# PixelClockController.net
KiCad netlist of a schematic drawn in Altium Designer
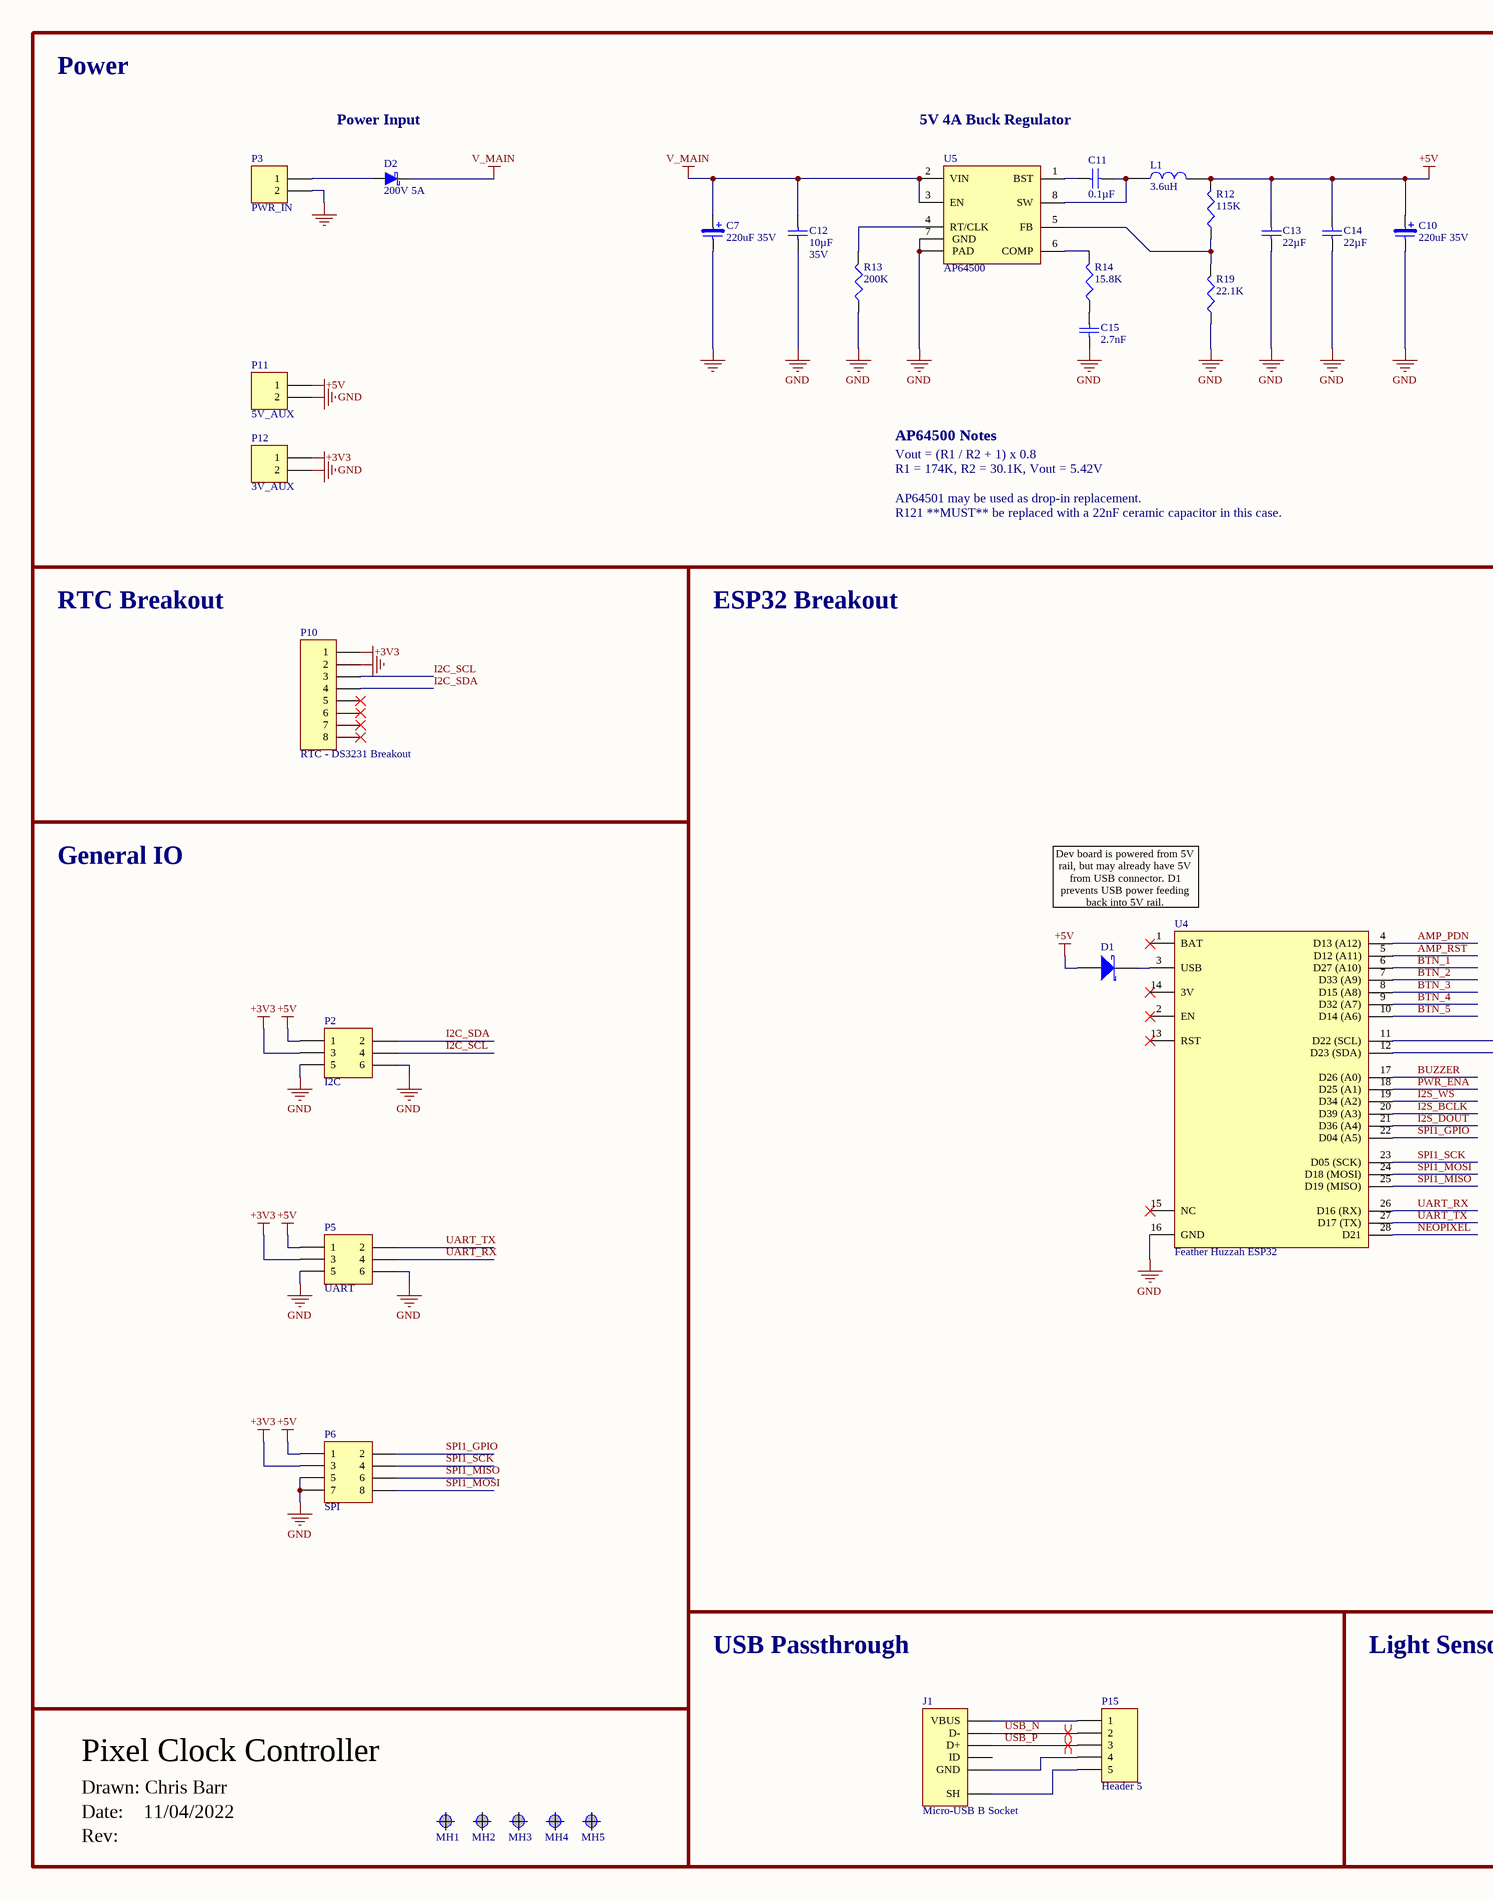
[diagram p0: PixelClockController.SchDoc, left]
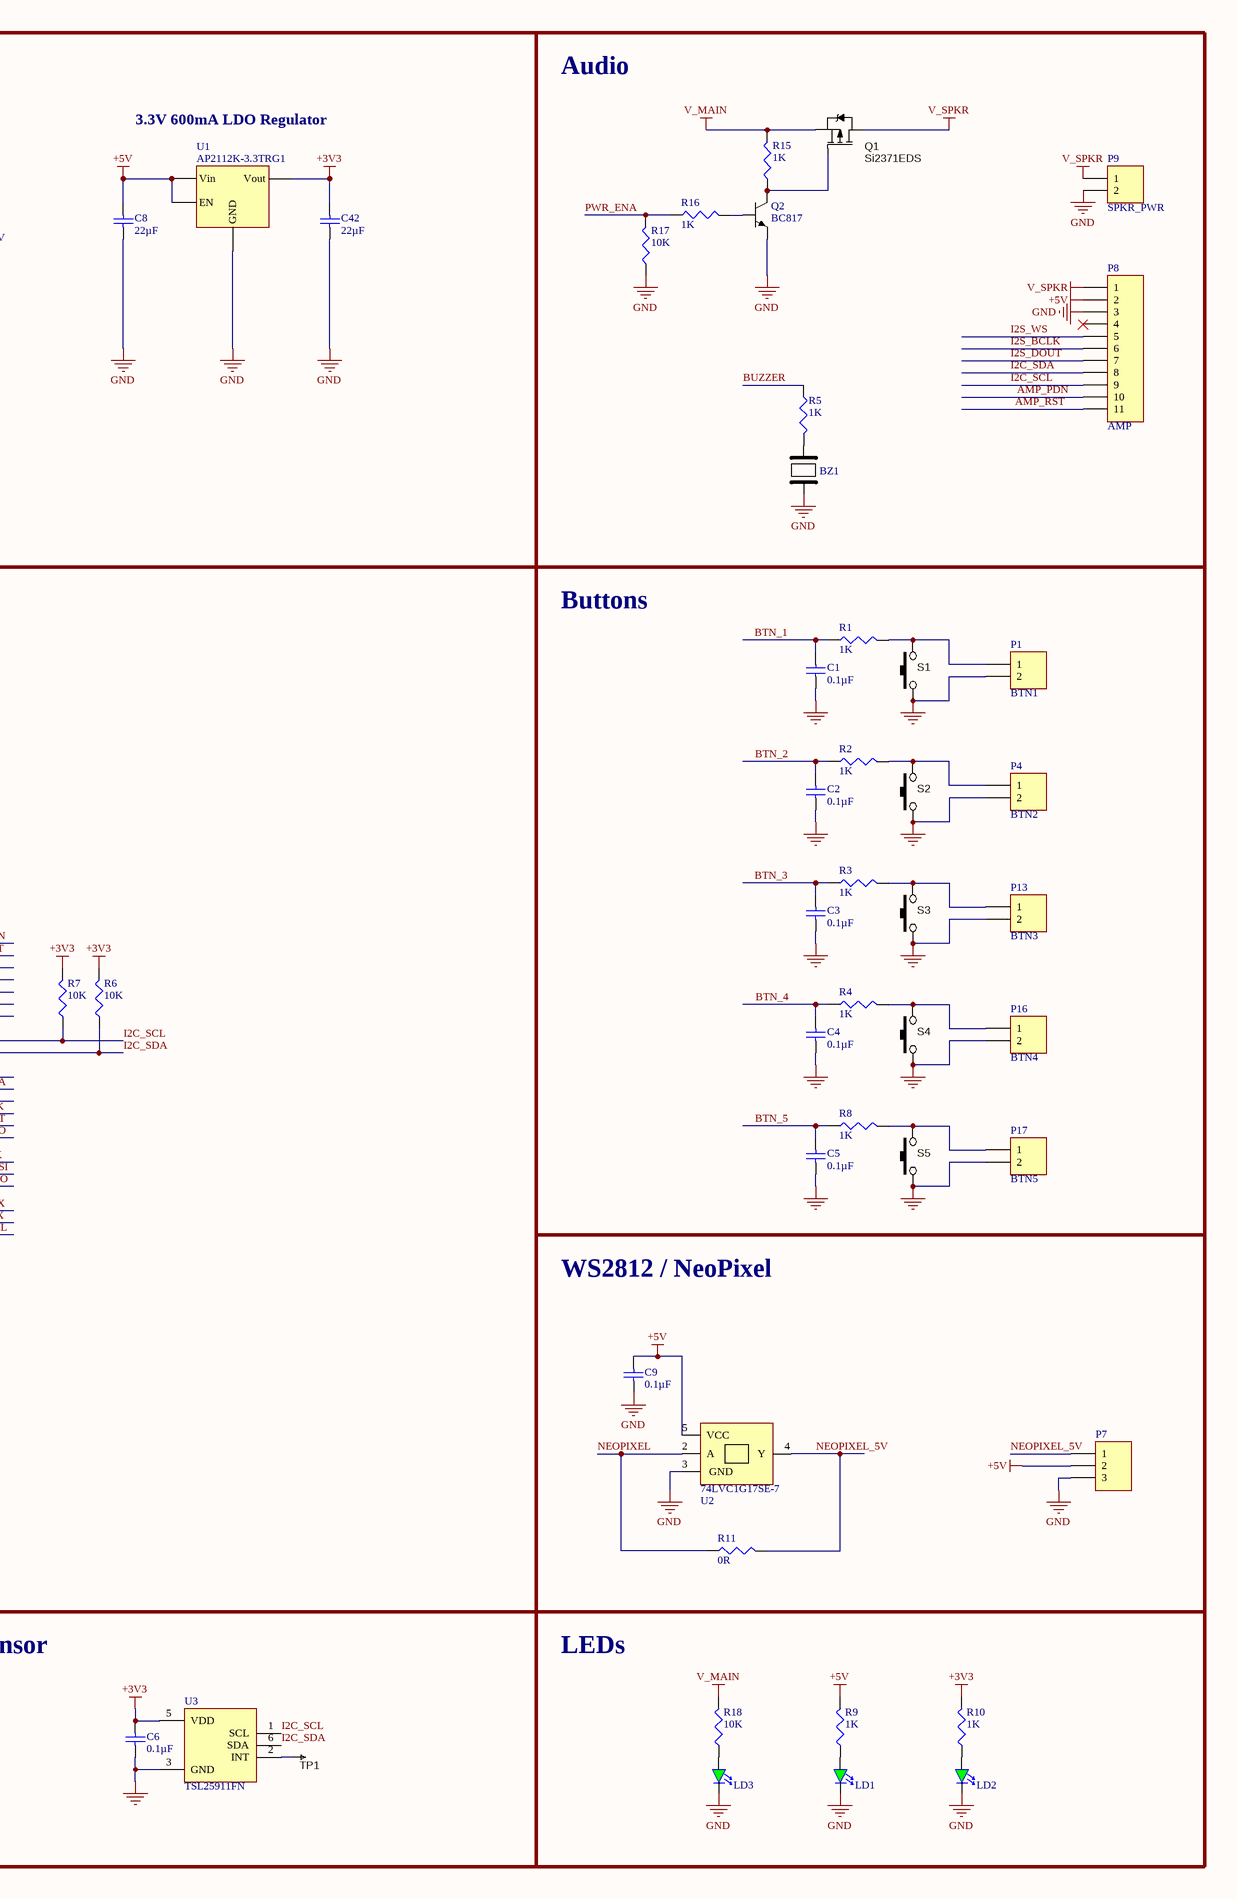
[diagram p1: PixelClockController.SchDoc, right]

(export (version "E")
  (design (tool "Eeschema 10.0.6"))
  (components
    (comp (ref "BZ1")
      (value "Piezo Transducer")
      (footprint "main_library:PKMCS0909E4000-R1")
      (description "AUDIO PIEZO TRANSDUCER 12.5V SMD 9 x 9MM")
      (libsource (lib "main_library") (part "Piezo Transducer"))
    )
    (comp (ref "C1")
      (value "0.1µF")
      (footprint "CAPC1608X90N")
      (description "CAP CER 0.1UF 50V X7R 0603")
      (fields (field (name "VOLTAGE") "50V") (field (name "TOLERANCE") "±10%"))
      (libsource (lib "Ceramic Cap DBLIB") (part "Capacitor"))
    )
    (comp (ref "C2")
      (value "0.1µF")
      (footprint "CAPC1608X90N")
      (description "CAP CER 0.1UF 50V X7R 0603")
      (fields (field (name "VOLTAGE") "50V") (field (name "TOLERANCE") "±10%"))
      (libsource (lib "Ceramic Cap DBLIB") (part "Capacitor"))
    )
    (comp (ref "C3")
      (value "0.1µF")
      (footprint "CAPC1608X90N")
      (description "CAP CER 0.1UF 50V X7R 0603")
      (fields (field (name "VOLTAGE") "50V") (field (name "TOLERANCE") "±10%"))
      (libsource (lib "Ceramic Cap DBLIB") (part "Capacitor"))
    )
    (comp (ref "C4")
      (value "0.1µF")
      (footprint "CAPC1608X90N")
      (description "CAP CER 0.1UF 50V X7R 0603")
      (fields (field (name "VOLTAGE") "50V") (field (name "TOLERANCE") "±10%"))
      (libsource (lib "Ceramic Cap DBLIB") (part "Capacitor"))
    )
    (comp (ref "C5")
      (value "0.1µF")
      (footprint "CAPC1608X90N")
      (description "CAP CER 0.1UF 50V X7R 0603")
      (fields (field (name "VOLTAGE") "50V") (field (name "TOLERANCE") "±10%"))
      (libsource (lib "Ceramic Cap DBLIB") (part "Capacitor"))
    )
    (comp (ref "C6")
      (value "0.1µF")
      (footprint "CAPC1608X90N")
      (description "CAP CER 0.1UF 50V X7R 0603")
      (fields (field (name "VOLTAGE") "50V") (field (name "TOLERANCE") "±10%"))
      (libsource (lib "Ceramic Cap DBLIB") (part "Capacitor"))
    )
    (comp (ref "C7")
      (value "220uF 35V")
      (footprint "CAPAE250P680X1220_VERT")
      (description "CAP ALUM 220UF 20% 35V RADIAL")
      (fields (field (name "Comment") "CapE-8.0-THT-220uF-35V") (field (name "PUBLISHER") "Altium Limited"))
      (libsource (lib "main_library") (part "CapE-8.0-THT-220uF-35V"))
    )
    (comp (ref "C8")
      (value "22µF")
      (footprint "CAPC3216X100N")
      (description "CAP CER 22UF 16V X5R 1206")
      (fields (field (name "VOLTAGE") "16V") (field (name "TOLERANCE") "±10%"))
      (libsource (lib "Ceramic Cap DBLIB") (part "Capacitor"))
    )
    (comp (ref "C9")
      (value "0.1µF")
      (footprint "CAPC1608X90N")
      (description "CAP CER 0.1UF 50V X7R 0603")
      (fields (field (name "VOLTAGE") "50V") (field (name "TOLERANCE") "±10%"))
      (libsource (lib "Ceramic Cap DBLIB") (part "Capacitor"))
    )
    (comp (ref "C10")
      (value "220uF 35V")
      (footprint "CAPAE250P680X1220_VERT")
      (description "CAP ALUM 220UF 20% 35V RADIAL")
      (fields (field (name "Comment") "CapE-8.0-THT-220uF-35V") (field (name "PUBLISHER") "Altium Limited"))
      (libsource (lib "main_library") (part "CapE-8.0-THT-220uF-35V"))
    )
    (comp (ref "C11")
      (value "0.1µF")
      (footprint "CAPC1608X90N")
      (description "CAP CER 0.1UF 50V X7R 0603")
      (fields (field (name "VOLTAGE") "50V") (field (name "TOLERANCE") "±10%"))
      (libsource (lib "Ceramic Cap DBLIB") (part "Capacitor"))
    )
    (comp (ref "C12")
      (value "10µF")
      (footprint "CAPC3225X220N")
      (description "CAP CER 10UF 35V X7R 1210")
      (fields
        (field (name "TOLERANCE") "±10%")
        (field (name "VOLTAGE") "35V")
        (field (name "Comment") "Capacitor")
      )
      (libsource (lib "Ceramic Cap DBLIB") (part "Capacitor"))
    )
    (comp (ref "C13")
      (value "22µF")
      (footprint "CAPC3216X100N")
      (description "CAP CER 22UF 16V X5R 1206")
      (fields (field (name "VOLTAGE") "16V") (field (name "TOLERANCE") "±10%"))
      (libsource (lib "Ceramic Cap DBLIB") (part "Capacitor"))
    )
    (comp (ref "C14")
      (value "22µF")
      (footprint "CAPC3216X100N")
      (description "CAP CER 22UF 16V X5R 1206")
      (fields (field (name "VOLTAGE") "16V") (field (name "TOLERANCE") "±10%"))
      (libsource (lib "Ceramic Cap DBLIB") (part "Capacitor"))
    )
    (comp (ref "C15")
      (value "2.7nF")
      (footprint "CAPC1608X90N")
      (description "CAP CER 2700PF 50V X7R 0603")
      (fields (field (name "VOLTAGE") "100V") (field (name "TOLERANCE") "±10%"))
      (libsource (lib "Ceramic Cap DBLIB") (part "Capacitor"))
    )
    (comp (ref "C42")
      (value "22µF")
      (footprint "CAPC3216X100N")
      (description "CAP CER 22UF 16V X5R 1206")
      (fields (field (name "VOLTAGE") "16V") (field (name "TOLERANCE") "±10%"))
      (libsource (lib "Ceramic Cap DBLIB") (part "Capacitor"))
    )
    (comp (ref "D1")
      (value "~")
      (footprint "DIOM2616X08N")
      (description "DIODE SCHOTTKY 40V 2A SOD123F")
      (fields (field (name "PUBLISHER") "Altium Limited"))
      (libsource (lib "picoprint_library") (part "Diode Schottky 2A 40V (SS24FL)"))
    )
    (comp (ref "D2")
      (value "200V 5A")
      (footprint "DO-214AA")
      (description "DIODE SCHOTTKY 200V 5A SMB")
      (fields (field (name "Comment") "Diode SK520BTR") (field (name "PUBLISHER") "Altium Limited"))
      (libsource (lib "main_library") (part "Diode SK520BTR"))
    )
    (comp (ref "J1")
      (value "Micro-USB B Socket")
      (footprint "USB3131-XX-0230-X_revB")
      (description "MICRO B SKT, VERTICAL, TH, 30\",")
      (libsource (lib "main_library") (part "Micro-USB B Socket Vertical"))
    )
    (comp (ref "L1")
      (value "3.6uH")
      (footprint "main_library:INDUCTOR_NR8040")
      (description "FIXED IND 3.6UH 4.9A 19.5 MOHM")
      (fields (field (name "Comment") "Inductor SMD 3.6uH 4.9A") (field (name "PUBLISHER") "Altium Limited"))
      (libsource (lib "main_library") (part "Inductor SMD 3.6uH 4.9A"))
    )
    (comp (ref "LD1")
      (value "LEDG  0603")
      (footprint "LED 1608-0603")
      (description "LED GREEN CLEAR CHIP SMD 0603")
      (libsource (lib "main_library") (part "LEDG  0603"))
    )
    (comp (ref "LD2")
      (value "LEDG  0603")
      (footprint "LED 1608-0603")
      (description "LED GREEN CLEAR CHIP SMD 0603")
      (libsource (lib "main_library") (part "LEDG  0603"))
    )
    (comp (ref "LD3")
      (value "LEDG  0603")
      (footprint "LED 1608-0603")
      (description "LED GREEN CLEAR CHIP SMD 0603")
      (libsource (lib "main_library") (part "LEDG  0603"))
    )
    (comp (ref "MH1")
      (value "Screw Hole")
      (footprint "M3-Hole-2")
      (libsource (lib "main_library") (part "Screw Hole"))
    )
    (comp (ref "MH2")
      (value "Screw Hole")
      (footprint "M3-Hole-2")
      (libsource (lib "main_library") (part "Screw Hole"))
    )
    (comp (ref "MH3")
      (value "Screw Hole")
      (footprint "M3-Hole-2")
      (libsource (lib "main_library") (part "Screw Hole"))
    )
    (comp (ref "MH4")
      (value "Screw Hole")
      (footprint "M3-Hole-2")
      (libsource (lib "main_library") (part "Screw Hole"))
    )
    (comp (ref "MH5")
      (value "Screw Hole")
      (footprint "M3-Hole-2")
      (libsource (lib "main_library") (part "Screw Hole"))
    )
    (comp (ref "P1")
      (value "BTN1")
      (footprint "HDR1X2-HEADER")
      (description "Header, 2-Pin")
      (libsource (lib "main_library") (part "Header 1X2"))
    )
    (comp (ref "P2")
      (value "I2C")
      (footprint "HDR2X3-Header")
      (description "Header, 3-Pin, Dual row")
      (libsource (lib "main_library") (part "Header 2X3"))
    )
    (comp (ref "P3")
      (value "PWR_IN")
      (footprint "HDR1X2-HEADER")
      (description "Header, 2-Pin")
      (libsource (lib "") (part "Header 1X2_1"))
    )
    (comp (ref "P4")
      (value "BTN2")
      (footprint "HDR1X2-HEADER")
      (description "Header, 2-Pin")
      (libsource (lib "main_library") (part "Header 1X2"))
    )
    (comp (ref "P5")
      (value "UART")
      (footprint "HDR2X3-Header")
      (description "Header, 3-Pin, Dual row")
      (libsource (lib "main_library") (part "Header 2X3"))
    )
    (comp (ref "P6")
      (value "SPI")
      (footprint "HDR2X4-HEADER")
      (description "Header, 4-Pin, Dual row")
      (libsource (lib "main_library") (part "Header 2X4"))
    )
    (comp (ref "P7")
      (value "Header 3")
      (footprint "HDR1X3-HEADER")
      (description "Header, 3-Pin")
      (libsource (lib "main_library") (part "Header 1X3"))
    )
    (comp (ref "P8")
      (value "AMP")
      (footprint "HDR1X11")
      (description "Header, 11-Pin")
      (fields (field (name "PUBLISHER") "Altium Limited"))
      (libsource (lib "Miscellaneous Connectors") (part "Header 11"))
    )
    (comp (ref "P9")
      (value "SPKR_PWR")
      (footprint "HDR1X2-HEADER")
      (description "Header, 2-Pin")
      (libsource (lib "main_library") (part "Header 1X2"))
    )
    (comp (ref "P10")
      (value "RTC - DS3231 Breakout")
      (footprint "HDR1X8-HEADER")
      (description "Header, 8-Pin")
      (libsource (lib "main_library") (part "Header 1X8"))
    )
    (comp (ref "P11")
      (value "5V_AUX")
      (footprint "HDR1X2-HEADER")
      (description "Header, 2-Pin")
      (libsource (lib "") (part "Header 1X2_1"))
    )
    (comp (ref "P12")
      (value "3V_AUX")
      (footprint "HDR1X2-HEADER")
      (description "Header, 2-Pin")
      (libsource (lib "") (part "Header 1X2_1"))
    )
    (comp (ref "P13")
      (value "BTN3")
      (footprint "HDR1X2-HEADER")
      (description "Header, 2-Pin")
      (libsource (lib "main_library") (part "Header 1X2"))
    )
    (comp (ref "P15")
      (value "Header 5")
      (footprint "HDR1X5")
      (description "Header, 5-Pin")
      (fields (field (name "PUBLISHER") "Altium Limited"))
      (libsource (lib "Miscellaneous Connectors") (part "Header 5"))
    )
    (comp (ref "P16")
      (value "BTN4")
      (footprint "HDR1X2-HEADER")
      (description "Header, 2-Pin")
      (libsource (lib "main_library") (part "Header 1X2"))
    )
    (comp (ref "P17")
      (value "BTN5")
      (footprint "HDR1X2-HEADER")
      (description "Header, 2-Pin")
      (libsource (lib "main_library") (part "Header 1X2"))
    )
    (comp (ref "Q1")
      (value "Si2371EDS")
      (footprint "SOT23-3 New")
      (description "MOSFET SMD P-CH 30V 4.8A SOT-23-3")
      (libsource (lib "main_library") (part "MOSFET - Si2371EDS"))
    )
    (comp (ref "Q2")
      (value "BC817")
      (footprint "SOT23-3 New")
      (description "TRANS NPN 45V 500MA TO236AB")
      (libsource (lib "main_library") (part "Transistor - NPN - 45V 500MA - BC817"))
    )
    (comp (ref "R1")
      (value "1K")
      (footprint "RES 1608-0603")
      (description "RES SMD 1K OHM 1% 1/10W 0603")
      (fields
        (field (name "TOLERANCE") "±1%")
        (field (name "Comment") "Resistor")
        (field (name "PUBLISHER") "Altium Limited")
      )
      (libsource (lib "Database_Libs1") (part "Resistor"))
    )
    (comp (ref "R2")
      (value "1K")
      (footprint "RES 1608-0603")
      (description "RES SMD 1K OHM 1% 1/10W 0603")
      (fields
        (field (name "TOLERANCE") "±1%")
        (field (name "Comment") "Resistor")
        (field (name "PUBLISHER") "Altium Limited")
      )
      (libsource (lib "Database_Libs1") (part "Resistor"))
    )
    (comp (ref "R3")
      (value "1K")
      (footprint "RES 1608-0603")
      (description "RES SMD 1K OHM 1% 1/10W 0603")
      (fields
        (field (name "TOLERANCE") "±1%")
        (field (name "Comment") "Resistor")
        (field (name "PUBLISHER") "Altium Limited")
      )
      (libsource (lib "Database_Libs1") (part "Resistor"))
    )
    (comp (ref "R4")
      (value "1K")
      (footprint "RES 1608-0603")
      (description "RES SMD 1K OHM 1% 1/10W 0603")
      (fields
        (field (name "TOLERANCE") "±1%")
        (field (name "Comment") "Resistor")
        (field (name "PUBLISHER") "Altium Limited")
      )
      (libsource (lib "Database_Libs1") (part "Resistor"))
    )
    (comp (ref "R5")
      (value "1K")
      (footprint "RES 1608-0603")
      (description "RES SMD 1K OHM 1% 1/10W 0603")
      (fields
        (field (name "TOLERANCE") "±1%")
        (field (name "Comment") "Resistor")
        (field (name "PUBLISHER") "Altium Limited")
      )
      (libsource (lib "Database_Libs1") (part "Resistor"))
    )
    (comp (ref "R6")
      (value "10K")
      (footprint "RES 1608-0603")
      (description "RES SMD 10K OHM 1% 1/10W 0603")
      (fields
        (field (name "TOLERANCE") "±1%")
        (field (name "Comment") "Resistor")
        (field (name "PUBLISHER") "Altium Limited")
      )
      (libsource (lib "Database_Libs1") (part "Resistor"))
    )
    (comp (ref "R7")
      (value "10K")
      (footprint "RES 1608-0603")
      (description "RES SMD 10K OHM 1% 1/10W 0603")
      (fields
        (field (name "TOLERANCE") "±1%")
        (field (name "Comment") "Resistor")
        (field (name "PUBLISHER") "Altium Limited")
      )
      (libsource (lib "Database_Libs1") (part "Resistor"))
    )
    (comp (ref "R8")
      (value "1K")
      (footprint "RES 1608-0603")
      (description "RES SMD 1K OHM 1% 1/10W 0603")
      (fields
        (field (name "TOLERANCE") "±1%")
        (field (name "Comment") "Resistor")
        (field (name "PUBLISHER") "Altium Limited")
      )
      (libsource (lib "Database_Libs1") (part "Resistor"))
    )
    (comp (ref "R9")
      (value "1K")
      (footprint "RES 1608-0603")
      (description "RES SMD 1K OHM 1% 1/10W 0603")
      (fields
        (field (name "TOLERANCE") "±1%")
        (field (name "Comment") "Resistor")
        (field (name "PUBLISHER") "Altium Limited")
      )
      (libsource (lib "Database_Libs1") (part "Resistor"))
    )
    (comp (ref "R10")
      (value "1K")
      (footprint "RES 1608-0603")
      (description "RES SMD 1K OHM 1% 1/10W 0603")
      (fields
        (field (name "TOLERANCE") "±1%")
        (field (name "Comment") "Resistor")
        (field (name "PUBLISHER") "Altium Limited")
      )
      (libsource (lib "Database_Libs1") (part "Resistor"))
    )
    (comp (ref "R11")
      (value "0R")
      (footprint "RES 1608-0603")
      (description "RES 0 OHM JUMPER 1/10W 0603")
      (fields (field (name "Comment") "Res-0603-0R") (field (name "PUBLISHER") "Altium Limited"))
      (libsource (lib "main_library") (part "Res-0603-0R"))
    )
    (comp (ref "R12")
      (value "115K")
      (footprint "RES 1608-0603")
      (description "RES SMD 115K OHM 1% 1/10W 0603")
      (fields
        (field (name "TOLERANCE") "±1%")
        (field (name "Comment") "Resistor")
        (field (name "PUBLISHER") "Altium Limited")
      )
      (libsource (lib "Database_Libs1") (part "Resistor"))
    )
    (comp (ref "R13")
      (value "200K")
      (footprint "RES 1608-0603")
      (description "RES SMD 200K OHM 1% 1/10W 0603")
      (fields
        (field (name "TOLERANCE") "±1%")
        (field (name "Comment") "Resistor")
        (field (name "PUBLISHER") "Altium Limited")
      )
      (libsource (lib "Database_Libs1") (part "Resistor"))
    )
    (comp (ref "R14")
      (value "15.8K")
      (footprint "RES 1608-0603")
      (description "RES SMD 15.8K OHM 1% 1/10W 0603")
      (fields
        (field (name "TOLERANCE") "±1%")
        (field (name "Comment") "Resistor")
        (field (name "PUBLISHER") "Altium Limited")
      )
      (libsource (lib "Database_Libs1") (part "Resistor"))
    )
    (comp (ref "R15")
      (value "1K")
      (footprint "RES 1608-0603")
      (description "RES SMD 1K OHM 1% 1/10W 0603")
      (fields
        (field (name "TOLERANCE") "±1%")
        (field (name "Comment") "Resistor")
        (field (name "PUBLISHER") "Altium Limited")
      )
      (libsource (lib "Database_Libs1") (part "Resistor"))
    )
    (comp (ref "R16")
      (value "1K")
      (footprint "RES 1608-0603")
      (description "RES SMD 1K OHM 1% 1/10W 0603")
      (fields
        (field (name "TOLERANCE") "±1%")
        (field (name "Comment") "Resistor")
        (field (name "PUBLISHER") "Altium Limited")
      )
      (libsource (lib "Database_Libs1") (part "Resistor"))
    )
    (comp (ref "R17")
      (value "10K")
      (footprint "RES 1608-0603")
      (description "RES SMD 10K OHM 1% 1/10W 0603")
      (fields
        (field (name "TOLERANCE") "±1%")
        (field (name "Comment") "Resistor")
        (field (name "PUBLISHER") "Altium Limited")
      )
      (libsource (lib "Database_Libs1") (part "Resistor"))
    )
    (comp (ref "R18")
      (value "10K")
      (footprint "RES 1608-0603")
      (description "RES SMD 10K OHM 1% 1/10W 0603")
      (fields
        (field (name "TOLERANCE") "±1%")
        (field (name "Comment") "Resistor")
        (field (name "PUBLISHER") "Altium Limited")
      )
      (libsource (lib "Database_Libs1") (part "Resistor"))
    )
    (comp (ref "R19")
      (value "22.1K")
      (footprint "RES 1608-0603")
      (description "RES SMD 22.1K OHM 1% 1/10W 0603")
      (fields
        (field (name "TOLERANCE") "±1%")
        (field (name "Comment") "Resistor")
        (field (name "PUBLISHER") "Altium Limited")
      )
      (libsource (lib "Database_Libs1") (part "Resistor"))
    )
    (comp (ref "S1")
      (value "SW_THT_PB_4.3mm")
      (footprint "TACT-SWITCH-TS1143")
      (description "6 X 6 MM, 12 MM ACTUATOR HEIGHT")
      (libsource (lib "PBL - Switches") (part "SW_THT_PB_4.3mm"))
    )
    (comp (ref "S2")
      (value "SW_THT_PB_4.3mm")
      (footprint "TACT-SWITCH-TS1143")
      (description "6 X 6 MM, 12 MM ACTUATOR HEIGHT")
      (libsource (lib "PBL - Switches") (part "SW_THT_PB_4.3mm"))
    )
    (comp (ref "S3")
      (value "SW_THT_PB_4.3mm")
      (footprint "TACT-SWITCH-TS1143")
      (description "6 X 6 MM, 12 MM ACTUATOR HEIGHT")
      (libsource (lib "PBL - Switches") (part "SW_THT_PB_4.3mm"))
    )
    (comp (ref "S4")
      (value "SW_THT_PB_4.3mm")
      (footprint "TACT-SWITCH-TS1143")
      (description "6 X 6 MM, 12 MM ACTUATOR HEIGHT")
      (libsource (lib "PBL - Switches") (part "SW_THT_PB_4.3mm"))
    )
    (comp (ref "S5")
      (value "SW_THT_PB_4.3mm")
      (footprint "TACT-SWITCH-TS1143")
      (description "6 X 6 MM, 12 MM ACTUATOR HEIGHT")
      (libsource (lib "PBL - Switches") (part "SW_THT_PB_4.3mm"))
    )
    (comp (ref "TP1")
      (value "TESTPOINT")
      (footprint "TP-R60")
      (description "SMD test pin")
      (libsource (lib "PBL - Test Points") (part "TESTPOINT"))
    )
    (comp (ref "U1")
      (value "AP2112K-3.3TRG1")
      (footprint "SOT23-5")
      (description "IC REG LINEAR 3.3V 600MA SOT25")
      (libsource (lib "picoprint_library") (part "Regulator - AP2112K 3.3V Linear Regulator"))
    )
    (comp (ref "U2")
      (value "74LVC1G17SE-7")
      (footprint "SOT353")
      (description "IC BUF NON-INVERT 5.5V SOT353")
      (libsource (lib "picoprint_library") (part "Buffer Non-Inverting Schmitt Trigger 74LVC1G17SE-7"))
    )
    (comp (ref "U3")
      (value "TSL25911FN")
      (footprint "SON65P200X70-6N")
      (description "SENSOR OPT AMBIENT 6DFN")
      (libsource (lib "main_library") (part "IC - Optical Sensor Ambient - I²C 6-WFDFN"))
    )
    (comp (ref "U4")
      (value "Feather Huzzah ESP32")
      (footprint "Adafruit Feather Huzzah ESP32")
      (libsource (lib "main_library") (part "Adafruit Feather - ESP32 Huzzah"))
    )
    (comp (ref "U5")
      (value "AP64500")
      (footprint "main_library:SOIC127P600X140_HS-9N")
      (description "IC DCDC CONV HV BUCK SO-8EP")
      (libsource (lib "main_library") (part "Regulator - AP64500 Buck Regulator"))
    )
  )
  (nets
    (net (code "1") (name "+3V3") (class "Default")
      (node (ref "C42") (pin "2") (pinfunction "2_2") (pintype "passive"))
      (node (ref "C6") (pin "2") (pinfunction "2_2") (pintype "passive"))
      (node (ref "P10") (pin "1") (pinfunction "1_1") (pintype "passive"))
      (node (ref "P12") (pin "1") (pinfunction "1_1") (pintype "passive"))
      (node (ref "P2") (pin "3") (pinfunction "3_3") (pintype "passive"))
      (node (ref "P5") (pin "3") (pinfunction "3_3") (pintype "passive"))
      (node (ref "P6") (pin "3") (pinfunction "3_3") (pintype "passive"))
      (node (ref "R10") (pin "2") (pinfunction "2_2") (pintype "passive"))
      (node (ref "R6") (pin "2") (pinfunction "2_2") (pintype "passive"))
      (node (ref "R7") (pin "2") (pinfunction "2_2") (pintype "passive"))
      (node (ref "U1") (pin "5") (pinfunction "Vout_5") (pintype "passive"))
      (node (ref "U3") (pin "5") (pinfunction "VDD_5") (pintype "passive"))
    )
    (net (code "2") (name "+5V") (class "Default")
      (node (ref "C10") (pin "1") (pinfunction "1_1") (pintype "passive"))
      (node (ref "C13") (pin "2") (pinfunction "2_2") (pintype "passive"))
      (node (ref "C14") (pin "2") (pinfunction "2_2") (pintype "passive"))
      (node (ref "C8") (pin "2") (pinfunction "2_2") (pintype "passive"))
      (node (ref "C9") (pin "2") (pinfunction "2_2") (pintype "passive"))
      (node (ref "D1") (pin "A") (pinfunction "A_A") (pintype "passive"))
      (node (ref "L1") (pin "2") (pinfunction "2_2") (pintype "passive"))
      (node (ref "P11") (pin "1") (pinfunction "1_1") (pintype "passive"))
      (node (ref "P2") (pin "1") (pinfunction "1_1") (pintype "passive"))
      (node (ref "P5") (pin "1") (pinfunction "1_1") (pintype "passive"))
      (node (ref "P6") (pin "1") (pinfunction "1_1") (pintype "passive"))
      (node (ref "P7") (pin "2") (pinfunction "2_2") (pintype "passive"))
      (node (ref "P8") (pin "2") (pinfunction "2_2") (pintype "passive"))
      (node (ref "R12") (pin "2") (pinfunction "2_2") (pintype "passive"))
      (node (ref "R9") (pin "2") (pinfunction "2_2") (pintype "passive"))
      (node (ref "U1") (pin "1") (pinfunction "Vin_1") (pintype "passive"))
      (node (ref "U1") (pin "3") (pinfunction "EN_3") (pintype "passive"))
      (node (ref "U2") (pin "5") (pinfunction "VCC_5") (pintype "passive"))
    )
    (net (code "3") (name "/AMP_PDN") (class "Default")
      (node (ref "P8") (pin "10") (pinfunction "10_10") (pintype "passive"))
      (node (ref "U4") (pin "4") (pinfunction "D13_(A12)_4") (pintype "passive"))
    )
    (net (code "4") (name "/AMP_RST") (class "Default")
      (node (ref "P8") (pin "11") (pinfunction "11_11") (pintype "passive"))
      (node (ref "U4") (pin "5") (pinfunction "D12_(A11)_5") (pintype "passive"))
    )
    (net (code "5") (name "/BTN_1") (class "Default")
      (node (ref "C1") (pin "2") (pinfunction "2_2") (pintype "passive"))
      (node (ref "R1") (pin "2") (pinfunction "2_2") (pintype "passive"))
      (node (ref "U4") (pin "6") (pinfunction "D27_(A10)_6") (pintype "passive"))
    )
    (net (code "6") (name "/BTN_2") (class "Default")
      (node (ref "C2") (pin "2") (pinfunction "2_2") (pintype "passive"))
      (node (ref "R2") (pin "2") (pinfunction "2_2") (pintype "passive"))
      (node (ref "U4") (pin "7") (pinfunction "D33_(A9)_7") (pintype "passive"))
    )
    (net (code "7") (name "/BTN_3") (class "Default")
      (node (ref "C3") (pin "2") (pinfunction "2_2") (pintype "passive"))
      (node (ref "R3") (pin "2") (pinfunction "2_2") (pintype "passive"))
      (node (ref "U4") (pin "8") (pinfunction "D15_(A8)_8") (pintype "passive"))
    )
    (net (code "8") (name "/BTN_4") (class "Default")
      (node (ref "C4") (pin "2") (pinfunction "2_2") (pintype "passive"))
      (node (ref "R4") (pin "2") (pinfunction "2_2") (pintype "passive"))
      (node (ref "U4") (pin "9") (pinfunction "D32_(A7)_9") (pintype "passive"))
    )
    (net (code "9") (name "/BTN_5") (class "Default")
      (node (ref "C5") (pin "2") (pinfunction "2_2") (pintype "passive"))
      (node (ref "R8") (pin "2") (pinfunction "2_2") (pintype "passive"))
      (node (ref "U4") (pin "10") (pinfunction "D14_(A6)_10") (pintype "passive"))
    )
    (net (code "10") (name "/BUZZER") (class "Default")
      (node (ref "R5") (pin "1") (pinfunction "1_1") (pintype "passive"))
      (node (ref "U4") (pin "17") (pinfunction "D26_(A0)_17") (pintype "passive"))
    )
    (net (code "11") (name "/I2C_SCL") (class "Default")
      (node (ref "P10") (pin "3") (pinfunction "3_3") (pintype "passive"))
      (node (ref "P2") (pin "4") (pinfunction "4_4") (pintype "passive"))
      (node (ref "P8") (pin "9") (pinfunction "9_9") (pintype "passive"))
      (node (ref "R7") (pin "1") (pinfunction "1_1") (pintype "passive"))
      (node (ref "U3") (pin "1") (pinfunction "SCL_1") (pintype "passive"))
      (node (ref "U4") (pin "11") (pinfunction "D22_(SCL)_11") (pintype "passive"))
    )
    (net (code "12") (name "/I2C_SDA") (class "Default")
      (node (ref "P10") (pin "4") (pinfunction "4_4") (pintype "passive"))
      (node (ref "P2") (pin "2") (pinfunction "2_2") (pintype "passive"))
      (node (ref "P8") (pin "8") (pinfunction "8_8") (pintype "passive"))
      (node (ref "R6") (pin "1") (pinfunction "1_1") (pintype "passive"))
      (node (ref "U3") (pin "6") (pinfunction "SDA_6") (pintype "passive"))
      (node (ref "U4") (pin "12") (pinfunction "D23_(SDA)_12") (pintype "passive"))
    )
    (net (code "13") (name "/I2S_BCLK") (class "Default")
      (node (ref "P8") (pin "6") (pinfunction "6_6") (pintype "passive"))
      (node (ref "U4") (pin "20") (pinfunction "D39_(A3)_20") (pintype "passive"))
    )
    (net (code "14") (name "/I2S_DOUT") (class "Default")
      (node (ref "P8") (pin "7") (pinfunction "7_7") (pintype "passive"))
      (node (ref "U4") (pin "21") (pinfunction "D36_(A4)_21") (pintype "passive"))
    )
    (net (code "15") (name "/I2S_WS") (class "Default")
      (node (ref "P8") (pin "5") (pinfunction "5_5") (pintype "passive"))
      (node (ref "U4") (pin "19") (pinfunction "D34_(A2)_19") (pintype "passive"))
    )
    (net (code "16") (name "/NEOPIXEL") (class "Default")
      (node (ref "R11") (pin "1") (pinfunction "1_1") (pintype "passive"))
      (node (ref "U2") (pin "2") (pinfunction "A_2") (pintype "passive"))
      (node (ref "U4") (pin "28") (pinfunction "D21_28") (pintype "passive"))
    )
    (net (code "17") (name "/NEOPIXEL_5V") (class "Default")
      (node (ref "P7") (pin "1") (pinfunction "1_1") (pintype "passive"))
      (node (ref "R11") (pin "2") (pinfunction "2_2") (pintype "passive"))
      (node (ref "U2") (pin "4") (pinfunction "Y_4") (pintype "passive"))
    )
    (net (code "18") (name "/PWR_ENA") (class "Default")
      (node (ref "R16") (pin "1") (pinfunction "1_1") (pintype "passive"))
      (node (ref "R17") (pin "2") (pinfunction "2_2") (pintype "passive"))
      (node (ref "U4") (pin "18") (pinfunction "D25_(A1)_18") (pintype "passive"))
    )
    (net (code "19") (name "/SPI1_GPIO") (class "Default")
      (node (ref "P6") (pin "2") (pinfunction "2_2") (pintype "passive"))
      (node (ref "U4") (pin "22") (pinfunction "D04_(A5)_22") (pintype "passive"))
    )
    (net (code "20") (name "/SPI1_MISO") (class "Default")
      (node (ref "P6") (pin "6") (pinfunction "6_6") (pintype "passive"))
      (node (ref "U4") (pin "25") (pinfunction "D19_(MISO)_25") (pintype "passive"))
    )
    (net (code "21") (name "/SPI1_MOSI") (class "Default")
      (node (ref "P6") (pin "8") (pinfunction "8_8") (pintype "passive"))
      (node (ref "U4") (pin "24") (pinfunction "D18_(MOSI)_24") (pintype "passive"))
    )
    (net (code "22") (name "/SPI1_SCK") (class "Default")
      (node (ref "P6") (pin "4") (pinfunction "4_4") (pintype "passive"))
      (node (ref "U4") (pin "23") (pinfunction "D05_(SCK)_23") (pintype "passive"))
    )
    (net (code "23") (name "/UART_RX") (class "Default")
      (node (ref "P5") (pin "4") (pinfunction "4_4") (pintype "passive"))
      (node (ref "U4") (pin "26") (pinfunction "D16_(RX)_26") (pintype "passive"))
    )
    (net (code "24") (name "/UART_TX") (class "Default")
      (node (ref "P5") (pin "2") (pinfunction "2_2") (pintype "passive"))
      (node (ref "U4") (pin "27") (pinfunction "D17_(TX)_27") (pintype "passive"))
    )
    (net (code "25") (name "/USB_N") (class "Default")
      (node (ref "J1") (pin "2") (pinfunction "D-_2") (pintype "passive"))
      (node (ref "P15") (pin "2") (pinfunction "2_2") (pintype "passive"))
    )
    (net (code "26") (name "/USB_P") (class "Default")
      (node (ref "J1") (pin "3") (pinfunction "D+_3") (pintype "passive"))
      (node (ref "P15") (pin "3") (pinfunction "3_3") (pintype "passive"))
    )
    (net (code "27") (name "GND") (class "Default")
      (node (ref "BZ1") (pin "2") (pinfunction "2_2") (pintype "passive"))
      (node (ref "C1") (pin "1") (pinfunction "1_1") (pintype "passive"))
      (node (ref "C10") (pin "2") (pinfunction "2_2") (pintype "passive"))
      (node (ref "C12") (pin "1") (pinfunction "1_1") (pintype "passive"))
      (node (ref "C13") (pin "1") (pinfunction "1_1") (pintype "passive"))
      (node (ref "C14") (pin "1") (pinfunction "1_1") (pintype "passive"))
      (node (ref "C15") (pin "1") (pinfunction "1_1") (pintype "passive"))
      (node (ref "C2") (pin "1") (pinfunction "1_1") (pintype "passive"))
      (node (ref "C3") (pin "1") (pinfunction "1_1") (pintype "passive"))
      (node (ref "C4") (pin "1") (pinfunction "1_1") (pintype "passive"))
      (node (ref "C42") (pin "1") (pinfunction "1_1") (pintype "passive"))
      (node (ref "C5") (pin "1") (pinfunction "1_1") (pintype "passive"))
      (node (ref "C6") (pin "1") (pinfunction "1_1") (pintype "passive"))
      (node (ref "C7") (pin "2") (pinfunction "2_2") (pintype "passive"))
      (node (ref "C8") (pin "1") (pinfunction "1_1") (pintype "passive"))
      (node (ref "C9") (pin "1") (pinfunction "1_1") (pintype "passive"))
      (node (ref "LD1") (pin "2") (pinfunction "K_2") (pintype "passive"))
      (node (ref "LD2") (pin "2") (pinfunction "K_2") (pintype "passive"))
      (node (ref "LD3") (pin "2") (pinfunction "K_2") (pintype "passive"))
      (node (ref "P1") (pin "2") (pinfunction "2_2") (pintype "passive"))
      (node (ref "P10") (pin "2") (pinfunction "2_2") (pintype "passive"))
      (node (ref "P11") (pin "2") (pinfunction "2_2") (pintype "passive"))
      (node (ref "P12") (pin "2") (pinfunction "2_2") (pintype "passive"))
      (node (ref "P13") (pin "2") (pinfunction "2_2") (pintype "passive"))
      (node (ref "P16") (pin "2") (pinfunction "2_2") (pintype "passive"))
      (node (ref "P17") (pin "2") (pinfunction "2_2") (pintype "passive"))
      (node (ref "P2") (pin "5") (pinfunction "5_5") (pintype "passive"))
      (node (ref "P2") (pin "6") (pinfunction "6_6") (pintype "passive"))
      (node (ref "P3") (pin "2") (pinfunction "2_2") (pintype "passive"))
      (node (ref "P4") (pin "2") (pinfunction "2_2") (pintype "passive"))
      (node (ref "P5") (pin "5") (pinfunction "5_5") (pintype "passive"))
      (node (ref "P5") (pin "6") (pinfunction "6_6") (pintype "passive"))
      (node (ref "P6") (pin "5") (pinfunction "5_5") (pintype "passive"))
      (node (ref "P6") (pin "7") (pinfunction "7_7") (pintype "passive"))
      (node (ref "P7") (pin "3") (pinfunction "3_3") (pintype "passive"))
      (node (ref "P8") (pin "3") (pinfunction "3_3") (pintype "passive"))
      (node (ref "P9") (pin "2") (pinfunction "2_2") (pintype "passive"))
      (node (ref "Q2") (pin "2") (pinfunction "E_2") (pintype "passive"))
      (node (ref "R13") (pin "1") (pinfunction "1_1") (pintype "passive"))
      (node (ref "R17") (pin "1") (pinfunction "1_1") (pintype "passive"))
      (node (ref "R19") (pin "1") (pinfunction "1_1") (pintype "passive"))
      (node (ref "S1") (pin "2") (pintype "passive"))
      (node (ref "S2") (pin "2") (pintype "passive"))
      (node (ref "S3") (pin "2") (pintype "passive"))
      (node (ref "S4") (pin "2") (pintype "passive"))
      (node (ref "S5") (pin "2") (pintype "passive"))
      (node (ref "U1") (pin "2") (pinfunction "GND_2") (pintype "passive"))
      (node (ref "U2") (pin "3") (pinfunction "GND_3") (pintype "passive"))
      (node (ref "U3") (pin "3") (pinfunction "GND_3") (pintype "passive"))
      (node (ref "U4") (pin "16") (pinfunction "GND_16") (pintype "passive"))
      (node (ref "U5") (pin "7") (pinfunction "GND_7") (pintype "passive"))
      (node (ref "U5") (pin "9") (pinfunction "PAD_9") (pintype "passive"))
    )
    (net (code "28") (name "Net-(BZ1-Pad1)") (class "Default")
      (node (ref "BZ1") (pin "1") (pinfunction "1_1") (pintype "passive"))
      (node (ref "R5") (pin "2") (pinfunction "2_2") (pintype "passive"))
    )
    (net (code "29") (name "Net-(C15-Pad2)") (class "Default")
      (node (ref "C15") (pin "2") (pinfunction "2_2") (pintype "passive"))
      (node (ref "R14") (pin "1") (pinfunction "1_1") (pintype "passive"))
    )
    (net (code "30") (name "Net-(D2-PadA)") (class "Default")
      (node (ref "D2") (pin "A") (pinfunction "A_A") (pintype "passive"))
      (node (ref "P3") (pin "1") (pinfunction "1_1") (pintype "passive"))
    )
    (net (code "31") (name "Net-(J1-GND)") (class "Default")
      (node (ref "J1") (pin "5") (pinfunction "GND_5") (pintype "passive"))
      (node (ref "P15") (pin "4") (pinfunction "4_4") (pintype "passive"))
    )
    (net (code "32") (name "Net-(J1-SH)") (class "Default")
      (node (ref "J1") (pin "S") (pinfunction "SH_S") (pintype "passive"))
      (node (ref "P15") (pin "5") (pinfunction "5_5") (pintype "passive"))
    )
    (net (code "33") (name "Net-(J1-VBUS)") (class "Default")
      (node (ref "J1") (pin "1") (pinfunction "VBUS_1") (pintype "passive"))
      (node (ref "P15") (pin "1") (pinfunction "1_1") (pintype "passive"))
    )
    (net (code "34") (name "Net-(LD1-A)") (class "Default")
      (node (ref "LD1") (pin "1") (pinfunction "A_1") (pintype "passive"))
      (node (ref "R9") (pin "1") (pinfunction "1_1") (pintype "passive"))
    )
    (net (code "35") (name "Net-(LD2-A)") (class "Default")
      (node (ref "LD2") (pin "1") (pinfunction "A_1") (pintype "passive"))
      (node (ref "R10") (pin "1") (pinfunction "1_1") (pintype "passive"))
    )
    (net (code "36") (name "Net-(LD3-A)") (class "Default")
      (node (ref "LD3") (pin "1") (pinfunction "A_1") (pintype "passive"))
      (node (ref "R18") (pin "1") (pinfunction "1_1") (pintype "passive"))
    )
    (net (code "37") (name "Net-(P1-Pad1)") (class "Default")
      (node (ref "P1") (pin "1") (pinfunction "1_1") (pintype "passive"))
      (node (ref "R1") (pin "1") (pinfunction "1_1") (pintype "passive"))
      (node (ref "S1") (pin "1") (pintype "passive"))
    )
    (net (code "38") (name "Net-(P4-Pad1)") (class "Default")
      (node (ref "P4") (pin "1") (pinfunction "1_1") (pintype "passive"))
      (node (ref "R2") (pin "1") (pinfunction "1_1") (pintype "passive"))
      (node (ref "S2") (pin "1") (pintype "passive"))
    )
    (net (code "39") (name "Net-(P13-Pad1)") (class "Default")
      (node (ref "P13") (pin "1") (pinfunction "1_1") (pintype "passive"))
      (node (ref "R3") (pin "1") (pinfunction "1_1") (pintype "passive"))
      (node (ref "S3") (pin "1") (pintype "passive"))
    )
    (net (code "40") (name "Net-(P16-Pad1)") (class "Default")
      (node (ref "P16") (pin "1") (pinfunction "1_1") (pintype "passive"))
      (node (ref "R4") (pin "1") (pinfunction "1_1") (pintype "passive"))
      (node (ref "S4") (pin "1") (pintype "passive"))
    )
    (net (code "41") (name "Net-(P17-Pad1)") (class "Default")
      (node (ref "P17") (pin "1") (pinfunction "1_1") (pintype "passive"))
      (node (ref "R8") (pin "1") (pinfunction "1_1") (pintype "passive"))
      (node (ref "S5") (pin "1") (pintype "passive"))
    )
    (net (code "42") (name "Net-(Q1-G)") (class "Default")
      (node (ref "Q1") (pin "1") (pinfunction "G_1") (pintype "passive"))
      (node (ref "Q2") (pin "3") (pinfunction "C_3") (pintype "passive"))
      (node (ref "R15") (pin "1") (pinfunction "1_1") (pintype "passive"))
    )
    (net (code "43") (name "Net-(Q2-B)") (class "Default")
      (node (ref "Q2") (pin "1") (pinfunction "B_1") (pintype "passive"))
      (node (ref "R16") (pin "2") (pinfunction "2_2") (pintype "passive"))
    )
    (net (code "44") (name "Net-(U3-INT)") (class "Default")
      (node (ref "TP1") (pin "1") (pintype "passive"))
      (node (ref "U3") (pin "2") (pinfunction "INT_2") (pintype "passive"))
    )
    (net (code "45") (name "Net-(U4-USB)") (class "Default")
      (node (ref "D1") (pin "K") (pinfunction "K_K") (pintype "passive"))
      (node (ref "U4") (pin "3") (pinfunction "USB_3") (pintype "passive"))
    )
    (net (code "46") (name "Net-(U5-BST)") (class "Default")
      (node (ref "C11") (pin "2") (pinfunction "2_2") (pintype "passive"))
      (node (ref "U5") (pin "1") (pinfunction "BST_1") (pintype "passive"))
    )
    (net (code "47") (name "Net-(U5-COMP)") (class "Default")
      (node (ref "R14") (pin "2") (pinfunction "2_2") (pintype "passive"))
      (node (ref "U5") (pin "6") (pinfunction "COMP_6") (pintype "passive"))
    )
    (net (code "48") (name "Net-(U5-FB)") (class "Default")
      (node (ref "R12") (pin "1") (pinfunction "1_1") (pintype "passive"))
      (node (ref "R19") (pin "2") (pinfunction "2_2") (pintype "passive"))
      (node (ref "U5") (pin "5") (pinfunction "FB_5") (pintype "passive"))
    )
    (net (code "49") (name "Net-(U5-RT{slash}CLK)") (class "Default")
      (node (ref "R13") (pin "2") (pinfunction "2_2") (pintype "passive"))
      (node (ref "U5") (pin "4") (pinfunction "RT/CLK_4") (pintype "passive"))
    )
    (net (code "50") (name "Net-(U5-SW)") (class "Default")
      (node (ref "C11") (pin "1") (pinfunction "1_1") (pintype "passive"))
      (node (ref "L1") (pin "1") (pinfunction "1_1") (pintype "passive"))
      (node (ref "U5") (pin "8") (pinfunction "SW_8") (pintype "passive"))
    )
    (net (code "51") (name "V_MAIN") (class "Default")
      (node (ref "C12") (pin "2") (pinfunction "2_2") (pintype "passive"))
      (node (ref "C7") (pin "1") (pinfunction "1_1") (pintype "passive"))
      (node (ref "D2") (pin "K") (pinfunction "K_K") (pintype "passive"))
      (node (ref "Q1") (pin "2") (pinfunction "S_2") (pintype "passive"))
      (node (ref "R15") (pin "2") (pinfunction "2_2") (pintype "passive"))
      (node (ref "R18") (pin "2") (pinfunction "2_2") (pintype "passive"))
      (node (ref "U5") (pin "2") (pinfunction "VIN_2") (pintype "passive"))
      (node (ref "U5") (pin "3") (pinfunction "EN_3") (pintype "passive"))
    )
    (net (code "52") (name "V_SPKR") (class "Default")
      (node (ref "P8") (pin "1") (pinfunction "1_1") (pintype "passive"))
      (node (ref "P9") (pin "1") (pinfunction "1_1") (pintype "passive"))
      (node (ref "Q1") (pin "3") (pinfunction "D_3") (pintype "passive"))
    )
    (net (code "53") (name "unconnected-(J1-ID-Pad4)") (class "Default")
      (node (ref "J1") (pin "4") (pinfunction "ID_4") (pintype "passive"))
    )
    (net (code "54") (name "unconnected-(MH1-0-PadM3)") (class "Default")
      (node (ref "MH1") (pin "M3") (pinfunction "0_M3") (pintype "passive"))
    )
    (net (code "55") (name "unconnected-(MH2-0-PadM3)") (class "Default")
      (node (ref "MH2") (pin "M3") (pinfunction "0_M3") (pintype "passive"))
    )
    (net (code "56") (name "unconnected-(MH3-0-PadM3)") (class "Default")
      (node (ref "MH3") (pin "M3") (pinfunction "0_M3") (pintype "passive"))
    )
    (net (code "57") (name "unconnected-(MH4-0-PadM3)") (class "Default")
      (node (ref "MH4") (pin "M3") (pinfunction "0_M3") (pintype "passive"))
    )
    (net (code "58") (name "unconnected-(MH5-0-PadM3)") (class "Default")
      (node (ref "MH5") (pin "M3") (pinfunction "0_M3") (pintype "passive"))
    )
    (net (code "59") (name "unconnected-(P8-Pad4)") (class "Default")
      (node (ref "P8") (pin "4") (pinfunction "4_4") (pintype "passive+no_connect"))
    )
    (net (code "60") (name "unconnected-(P10-Pad5)") (class "Default")
      (node (ref "P10") (pin "5") (pinfunction "5_5") (pintype "passive+no_connect"))
    )
    (net (code "61") (name "unconnected-(P10-Pad6)") (class "Default")
      (node (ref "P10") (pin "6") (pinfunction "6_6") (pintype "passive+no_connect"))
    )
    (net (code "62") (name "unconnected-(P10-Pad7)") (class "Default")
      (node (ref "P10") (pin "7") (pinfunction "7_7") (pintype "passive+no_connect"))
    )
    (net (code "63") (name "unconnected-(P10-Pad8)") (class "Default")
      (node (ref "P10") (pin "8") (pinfunction "8_8") (pintype "passive+no_connect"))
    )
    (net (code "64") (name "unconnected-(U4-3V-Pad14)") (class "Default")
      (node (ref "U4") (pin "14") (pinfunction "3V_14") (pintype "passive+no_connect"))
    )
    (net (code "65") (name "unconnected-(U4-BAT-Pad1)") (class "Default")
      (node (ref "U4") (pin "1") (pinfunction "BAT_1") (pintype "passive+no_connect"))
    )
    (net (code "66") (name "unconnected-(U4-EN-Pad2)") (class "Default")
      (node (ref "U4") (pin "2") (pinfunction "EN_2") (pintype "passive+no_connect"))
    )
    (net (code "67") (name "unconnected-(U4-NC-Pad15)") (class "Default")
      (node (ref "U4") (pin "15") (pinfunction "NC_15") (pintype "passive+no_connect"))
    )
    (net (code "68") (name "unconnected-(U4-RST-Pad13)") (class "Default")
      (node (ref "U4") (pin "13") (pinfunction "RST_13") (pintype "passive+no_connect"))
    )
  )
)
